# heater.net
KiCad netlist of a schematic drawn in Altium Designer
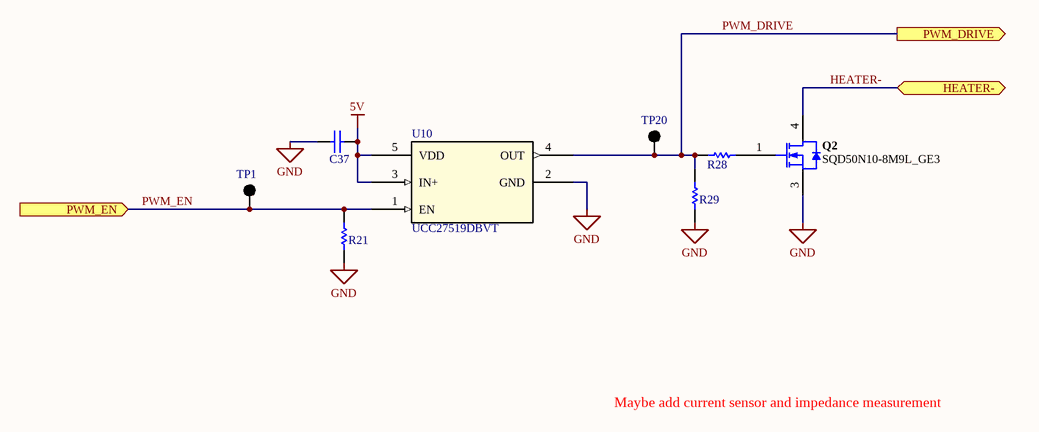
[diagram p0: heater.SchDoc]

(export (version "E")
  (design (tool "Eeschema 10.0.6"))
  (components
    (comp (ref "C37")
      (value "Generic 0805 Capacitor")
      (footprint "0805")
      (libsource (lib "symbol_library") (part "C_0805"))
    )
    (comp (ref "Q2")
      (value "SQD50N10-8M9L_GE3")
      (footprint "TO-252AA")
      (description "N-Channel 100V 50A (Tc) 136W (Tc) Surface Mount TO-252")
      (libsource (lib "symbol_library") (part "SQD50N10"))
    )
    (comp (ref "R21")
      (value "Generic 0603 Resistor")
      (footprint "0603")
      (libsource (lib "symbol_library") (part "R_0603"))
    )
    (comp (ref "R28")
      (value "Generic 0603 Resistor")
      (footprint "0603")
      (libsource (lib "symbol_library") (part "R_0603"))
    )
    (comp (ref "R29")
      (value "Generic 0603 Resistor")
      (footprint "0603")
      (libsource (lib "symbol_library") (part "R_0603"))
    )
    (comp (ref "TP1")
      (value "5001")
      (footprint "KSTN-5001")
      (description "Test Point, Black, 1-Pin THD, RoHS, Bulk")
      (fields (field (name "MANUFACTURER") "Keystone"))
      (libsource (lib "symbol_library") (part "TP5001"))
    )
    (comp (ref "TP20")
      (value "5001")
      (footprint "KSTN-5001")
      (description "Test Point, Black, 1-Pin THD, RoHS, Bulk")
      (fields (field (name "MANUFACTURER") "Keystone"))
      (libsource (lib "symbol_library") (part "TP5001"))
    )
    (comp (ref "U10")
      (value "UCC27519DBVT")
      (footprint "DBV5-M")
      (description "Low-Side Gate Driver IC Non-Inverting SOT-23-5")
      (libsource (lib "symbol_library") (part "UCC27519"))
    )
  )
  (nets
    (net (code "1") (name "/HEATER-") (class "Default")
      (node (ref "Q2") (pin "4") (pinfunction "D_4") (pintype "passive"))
    )
    (net (code "2") (name "/PWM_DRIVE") (class "Default")
      (node (ref "R28") (pin "1") (pinfunction "1_1") (pintype "passive"))
      (node (ref "R29") (pin "2") (pinfunction "2_2") (pintype "passive"))
      (node (ref "TP20") (pin "1") (pintype "passive"))
      (node (ref "U10") (pin "4") (pinfunction "OUT_4") (pintype "output"))
    )
    (net (code "3") (name "/PWM_EN") (class "Default")
      (node (ref "R21") (pin "2") (pinfunction "2_2") (pintype "passive"))
      (node (ref "TP1") (pin "1") (pintype "passive"))
      (node (ref "U10") (pin "1") (pinfunction "EN_1") (pintype "input"))
    )
    (net (code "4") (name "5V") (class "Default")
      (node (ref "C37") (pin "2") (pinfunction "2_2") (pintype "passive"))
      (node (ref "U10") (pin "3") (pinfunction "IN+_3") (pintype "input"))
      (node (ref "U10") (pin "5") (pinfunction "VDD_5") (pintype "power_in"))
    )
    (net (code "5") (name "GND") (class "Default")
      (node (ref "C37") (pin "1") (pinfunction "1_1") (pintype "passive"))
      (node (ref "Q2") (pin "3") (pinfunction "S_3") (pintype "passive"))
      (node (ref "R21") (pin "1") (pinfunction "1_1") (pintype "passive"))
      (node (ref "R29") (pin "1") (pinfunction "1_1") (pintype "passive"))
      (node (ref "U10") (pin "2") (pinfunction "GND_2") (pintype "power_in"))
    )
    (net (code "6") (name "Net-(Q2-G)") (class "Default")
      (node (ref "Q2") (pin "1") (pinfunction "G_1") (pintype "passive"))
      (node (ref "R28") (pin "2") (pinfunction "2_2") (pintype "passive"))
    )
  )
)
